# imu_board.net
KiCad netlist of a schematic drawn in EAGLE
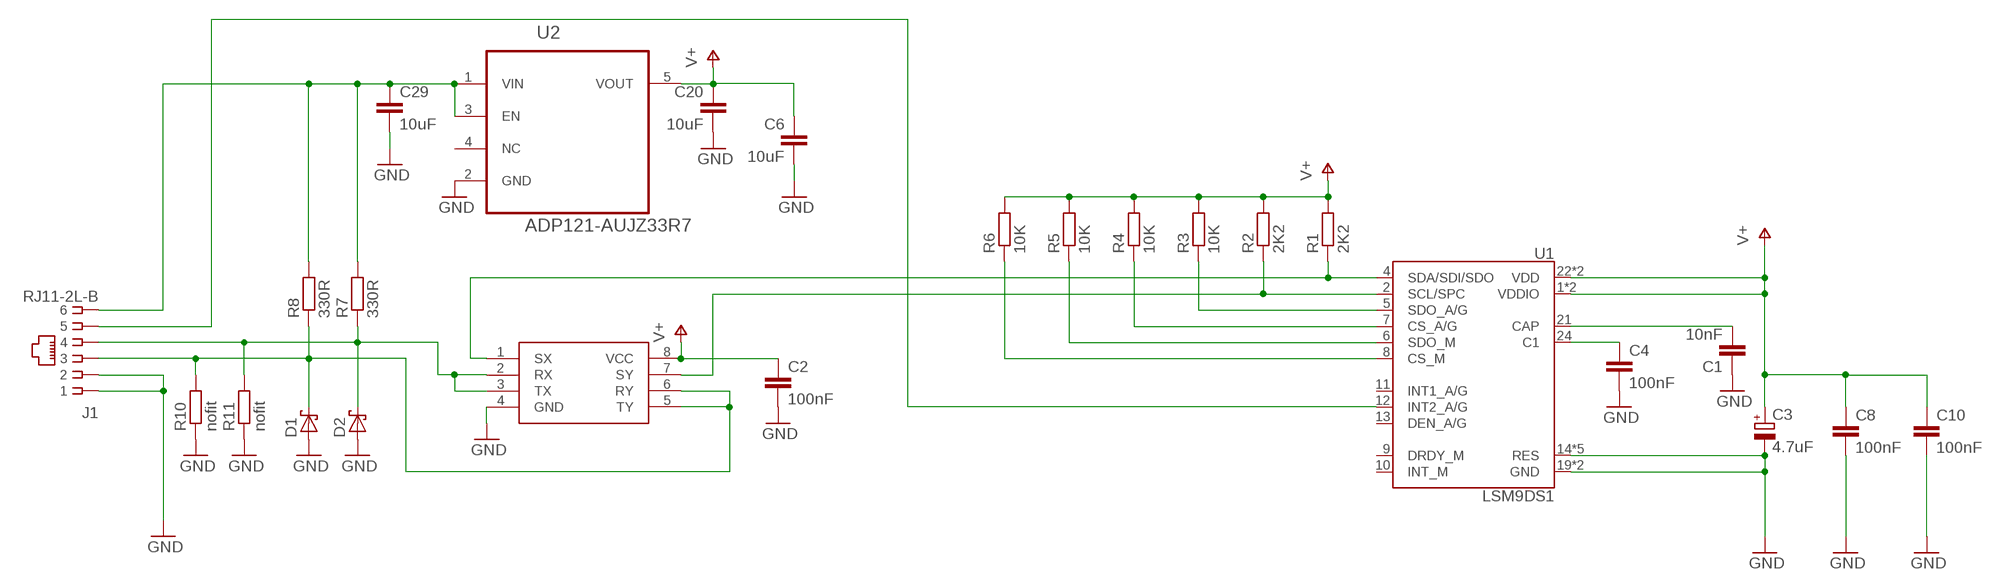
[diagram p0: schematic, sheet 1]

(export (version "E")
  (design (tool "Eeschema 10.0.6"))
  (components
    (comp (ref "C1")
      (value "10nF")
      (footprint "eagle-import:C0805")
      (libsource (lib "eagle-import") (part "C-EUC0805"))
    )
    (comp (ref "C2")
      (value "100nF")
      (footprint "eagle-import:C0805")
      (libsource (lib "eagle-import") (part "C-EUC0805"))
    )
    (comp (ref "C3")
      (value "4.7uF")
      (footprint "eagle-import:SMC_C")
      (libsource (lib "eagle-import") (part "CPOL-EUSMCC"))
    )
    (comp (ref "C4")
      (value "100nF")
      (footprint "eagle-import:C0805")
      (libsource (lib "eagle-import") (part "C-EUC0805"))
    )
    (comp (ref "C6")
      (value "10uF")
      (footprint "eagle-import:C1206")
      (libsource (lib "eagle-import") (part "C-EUC1206"))
    )
    (comp (ref "C8")
      (value "100nF")
      (footprint "eagle-import:C0805")
      (libsource (lib "eagle-import") (part "C-EUC0805"))
    )
    (comp (ref "C10")
      (value "100nF")
      (footprint "eagle-import:C0805")
      (libsource (lib "eagle-import") (part "C-EUC0805"))
    )
    (comp (ref "C20")
      (value "10uF")
      (footprint "eagle-import:C1206")
      (libsource (lib "eagle-import") (part "C-EUC1206"))
    )
    (comp (ref "C29")
      (value "10uF")
      (footprint "eagle-import:C1206")
      (libsource (lib "eagle-import") (part "C-EUC1206"))
    )
    (comp (ref "D1")
      (value "SCHOTTKY-DIODE")
      (footprint "eagle-import:DIODE_SMB")
      (libsource (lib "eagle-import") (part "SCHOTTKY-DIODE"))
    )
    (comp (ref "D2")
      (value "SCHOTTKY-DIODE")
      (footprint "eagle-import:DIODE_SMB")
      (libsource (lib "eagle-import") (part "SCHOTTKY-DIODE"))
    )
    (comp (ref "J1")
      (value "RJ11-2L-B")
      (footprint "eagle-import:RJ11-NO_SHIELD")
      (fields (field (name "MF") "TYCO ELECTRONICS"))
      (libsource (lib "eagle-import") (part "RJ11-2L-B"))
    )
    (comp (ref "R1")
      (value "2K2")
      (footprint "eagle-import:R0805")
      (libsource (lib "eagle-import") (part "R-EU_R0805"))
    )
    (comp (ref "R2")
      (value "2K2")
      (footprint "eagle-import:R0805")
      (libsource (lib "eagle-import") (part "R-EU_R0805"))
    )
    (comp (ref "R3")
      (value "10K")
      (footprint "eagle-import:R0805")
      (libsource (lib "eagle-import") (part "R-EU_R0805"))
    )
    (comp (ref "R4")
      (value "10K")
      (footprint "eagle-import:R0805")
      (libsource (lib "eagle-import") (part "R-EU_R0805"))
    )
    (comp (ref "R5")
      (value "10K")
      (footprint "eagle-import:R0805")
      (libsource (lib "eagle-import") (part "R-EU_R0805"))
    )
    (comp (ref "R6")
      (value "10K")
      (footprint "eagle-import:R0805")
      (libsource (lib "eagle-import") (part "R-EU_R0805"))
    )
    (comp (ref "R7")
      (value "330R")
      (footprint "eagle-import:R0805")
      (libsource (lib "eagle-import") (part "R-EU_R0805"))
    )
    (comp (ref "R8")
      (value "330R")
      (footprint "eagle-import:R0805")
      (libsource (lib "eagle-import") (part "R-EU_R0805"))
    )
    (comp (ref "R10")
      (value "nofit")
      (footprint "eagle-import:R1206")
      (libsource (lib "eagle-import") (part "R-EU_R1206"))
    )
    (comp (ref "R11")
      (value "nofit")
      (footprint "eagle-import:R1206")
      (libsource (lib "eagle-import") (part "R-EU_R1206"))
    )
    (comp (ref "U$1")
      (value "P82B96")
      (footprint "eagle-import:DIP8")
      (libsource (lib "eagle-import") (part "P82B96"))
    )
    (comp (ref "U1")
      (value "LSM9DS1")
      (footprint "eagle-import:LGA24-8X4")
      (libsource (lib "eagle-import") (part "LSM9DS1"))
    )
    (comp (ref "U2")
      (value "ADP121-AUJZ33R7")
      (footprint "eagle-import:SOT95P280X100-5N")
      (libsource (lib "eagle-import") (part "ADP121-AUJZ33R7"))
    )
  )
  (nets
    (net (code "1") (name "GND") (class "Default")
      (node (ref "C1") (pin "1") (pinfunction "1_1") (pintype "passive"))
      (node (ref "C10") (pin "2") (pinfunction "2_2") (pintype "passive"))
      (node (ref "C2") (pin "2") (pinfunction "2_2") (pintype "passive"))
      (node (ref "C20") (pin "2") (pinfunction "2_2") (pintype "passive"))
      (node (ref "C29") (pin "2") (pinfunction "2_2") (pintype "passive"))
      (node (ref "C3") (pin "-") (pinfunction "-_-") (pintype "passive"))
      (node (ref "C4") (pin "2") (pinfunction "2_2") (pintype "passive"))
      (node (ref "C6") (pin "2") (pinfunction "2_2") (pintype "passive"))
      (node (ref "C8") (pin "2") (pinfunction "2_2") (pintype "passive"))
      (node (ref "D1") (pin "A") (pinfunction "C_A") (pintype "passive"))
      (node (ref "D2") (pin "A") (pinfunction "C_A") (pintype "passive"))
      (node (ref "J1") (pin "1") (pinfunction "1_1") (pintype "passive"))
      (node (ref "J1") (pin "2") (pinfunction "2_2") (pintype "passive"))
      (node (ref "R10") (pin "1") (pinfunction "1_1") (pintype "passive"))
      (node (ref "R11") (pin "1") (pinfunction "1_1") (pintype "passive"))
      (node (ref "U$1") (pin "4") (pinfunction "GND_4") (pintype "bidirectional"))
      (node (ref "U1") (pin "14") (pinfunction "RES_14") (pintype "bidirectional"))
      (node (ref "U1") (pin "15") (pinfunction "RES_15") (pintype "bidirectional"))
      (node (ref "U1") (pin "16") (pinfunction "RES_16") (pintype "bidirectional"))
      (node (ref "U1") (pin "17") (pinfunction "RES_17") (pintype "bidirectional"))
      (node (ref "U1") (pin "18") (pinfunction "RES_18") (pintype "bidirectional"))
      (node (ref "U1") (pin "19") (pinfunction "GND_19") (pintype "bidirectional"))
      (node (ref "U1") (pin "20") (pinfunction "GND_20") (pintype "bidirectional"))
      (node (ref "U2") (pin "2") (pinfunction "GND_2") (pintype "passive"))
    )
    (net (code "2") (name "Net-(D1-A)") (class "Default")
      (node (ref "D1") (pin "C") (pinfunction "A_C") (pintype "passive"))
      (node (ref "J1") (pin "3") (pinfunction "3_3") (pintype "passive"))
      (node (ref "R10") (pin "2") (pinfunction "2_2") (pintype "passive"))
      (node (ref "R8") (pin "1") (pinfunction "1_1") (pintype "passive"))
      (node (ref "U$1") (pin "5") (pinfunction "TY_5") (pintype "bidirectional"))
      (node (ref "U$1") (pin "6") (pinfunction "RY_6") (pintype "bidirectional"))
    )
    (net (code "3") (name "Net-(D2-A)") (class "Default")
      (node (ref "D2") (pin "C") (pinfunction "A_C") (pintype "passive"))
      (node (ref "J1") (pin "4") (pinfunction "4_4") (pintype "passive"))
      (node (ref "R11") (pin "2") (pinfunction "2_2") (pintype "passive"))
      (node (ref "R7") (pin "1") (pinfunction "1_1") (pintype "passive"))
      (node (ref "U$1") (pin "2") (pinfunction "RX_2") (pintype "bidirectional"))
      (node (ref "U$1") (pin "3") (pinfunction "TX_3") (pintype "bidirectional"))
    )
    (net (code "4") (name "Net-(U$1-SX)") (class "Default")
      (node (ref "R1") (pin "1") (pinfunction "1_1") (pintype "passive"))
      (node (ref "U$1") (pin "1") (pinfunction "SX_1") (pintype "bidirectional"))
      (node (ref "U1") (pin "4") (pinfunction "SDA/SDI/SDO_4") (pintype "bidirectional"))
    )
    (net (code "5") (name "Net-(U$1-SY)") (class "Default")
      (node (ref "R2") (pin "1") (pinfunction "1_1") (pintype "passive"))
      (node (ref "U$1") (pin "7") (pinfunction "SY_7") (pintype "bidirectional"))
      (node (ref "U1") (pin "2") (pinfunction "SCL/SPC_2") (pintype "bidirectional"))
    )
    (net (code "6") (name "Net-(U1-C1)") (class "Default")
      (node (ref "C4") (pin "1") (pinfunction "1_1") (pintype "passive"))
      (node (ref "U1") (pin "24") (pinfunction "C1_24") (pintype "bidirectional"))
    )
    (net (code "7") (name "Net-(U1-CAP)") (class "Default")
      (node (ref "C1") (pin "2") (pinfunction "2_2") (pintype "passive"))
      (node (ref "U1") (pin "21") (pinfunction "CAP_21") (pintype "bidirectional"))
    )
    (net (code "8") (name "Net-(U1-CS_A{slash}G)") (class "Default")
      (node (ref "R4") (pin "1") (pinfunction "1_1") (pintype "passive"))
      (node (ref "U1") (pin "7") (pinfunction "CS_A/G_7") (pintype "bidirectional"))
    )
    (net (code "9") (name "Net-(U1-CS_M)") (class "Default")
      (node (ref "R6") (pin "1") (pinfunction "1_1") (pintype "passive"))
      (node (ref "U1") (pin "8") (pinfunction "CS_M_8") (pintype "bidirectional"))
    )
    (net (code "10") (name "Net-(U1-INT2_A{slash}G)") (class "Default")
      (node (ref "J1") (pin "5") (pinfunction "5_5") (pintype "passive"))
      (node (ref "U1") (pin "12") (pinfunction "INT2_A/G_12") (pintype "bidirectional"))
    )
    (net (code "11") (name "Net-(U1-SDO_A{slash}G)") (class "Default")
      (node (ref "R3") (pin "1") (pinfunction "1_1") (pintype "passive"))
      (node (ref "U1") (pin "5") (pinfunction "SDO_A/G_5") (pintype "bidirectional"))
    )
    (net (code "12") (name "Net-(U1-SDO_M)") (class "Default")
      (node (ref "R5") (pin "1") (pinfunction "1_1") (pintype "passive"))
      (node (ref "U1") (pin "6") (pinfunction "SDO_M_6") (pintype "bidirectional"))
    )
    (net (code "13") (name "Net-(U2-EN)") (class "Default")
      (node (ref "C29") (pin "1") (pinfunction "1_1") (pintype "passive"))
      (node (ref "J1") (pin "6") (pinfunction "6_6") (pintype "passive"))
      (node (ref "R7") (pin "2") (pinfunction "2_2") (pintype "passive"))
      (node (ref "R8") (pin "2") (pinfunction "2_2") (pintype "passive"))
      (node (ref "U2") (pin "1") (pinfunction "VIN_1") (pintype "input"))
      (node (ref "U2") (pin "3") (pinfunction "EN_3") (pintype "input"))
    )
    (net (code "14") (name "V+") (class "Default")
      (node (ref "C10") (pin "1") (pinfunction "1_1") (pintype "passive"))
      (node (ref "C2") (pin "1") (pinfunction "1_1") (pintype "passive"))
      (node (ref "C20") (pin "1") (pinfunction "1_1") (pintype "passive"))
      (node (ref "C3") (pin "+") (pinfunction "+_+") (pintype "passive"))
      (node (ref "C6") (pin "1") (pinfunction "1_1") (pintype "passive"))
      (node (ref "C8") (pin "1") (pinfunction "1_1") (pintype "passive"))
      (node (ref "R1") (pin "2") (pinfunction "2_2") (pintype "passive"))
      (node (ref "R2") (pin "2") (pinfunction "2_2") (pintype "passive"))
      (node (ref "R3") (pin "2") (pinfunction "2_2") (pintype "passive"))
      (node (ref "R4") (pin "2") (pinfunction "2_2") (pintype "passive"))
      (node (ref "R5") (pin "2") (pinfunction "2_2") (pintype "passive"))
      (node (ref "R6") (pin "2") (pinfunction "2_2") (pintype "passive"))
      (node (ref "U$1") (pin "8") (pinfunction "VCC_8") (pintype "bidirectional"))
      (node (ref "U1") (pin "1") (pinfunction "VDDIO_1") (pintype "bidirectional"))
      (node (ref "U1") (pin "22") (pinfunction "VDD_22") (pintype "bidirectional"))
      (node (ref "U1") (pin "23") (pinfunction "VDD_23") (pintype "bidirectional"))
      (node (ref "U1") (pin "3") (pinfunction "VDDIO_3") (pintype "bidirectional"))
      (node (ref "U2") (pin "5") (pinfunction "VOUT_5") (pintype "output"))
    )
    (net (code "15") (name "unconnected-(U1-DEN_A{slash}G-Pad13)") (class "Default")
      (node (ref "U1") (pin "13") (pinfunction "DEN_A/G_13") (pintype "bidirectional"))
    )
    (net (code "16") (name "unconnected-(U1-DRDY_M-Pad9)") (class "Default")
      (node (ref "U1") (pin "9") (pinfunction "DRDY_M_9") (pintype "bidirectional"))
    )
    (net (code "17") (name "unconnected-(U1-INT1_A{slash}G-Pad11)") (class "Default")
      (node (ref "U1") (pin "11") (pinfunction "INT1_A/G_11") (pintype "bidirectional"))
    )
    (net (code "18") (name "unconnected-(U1-INT_M-Pad10)") (class "Default")
      (node (ref "U1") (pin "10") (pinfunction "INT_M_10") (pintype "bidirectional"))
    )
    (net (code "19") (name "unconnected-(U2-NC-Pad4)") (class "Default")
      (node (ref "U2") (pin "4") (pinfunction "NC_4") (pintype "no_connect"))
    )
  )
)
